# PolluxSensorTemp.net
KiCad netlist of a schematic drawn in EAGLE
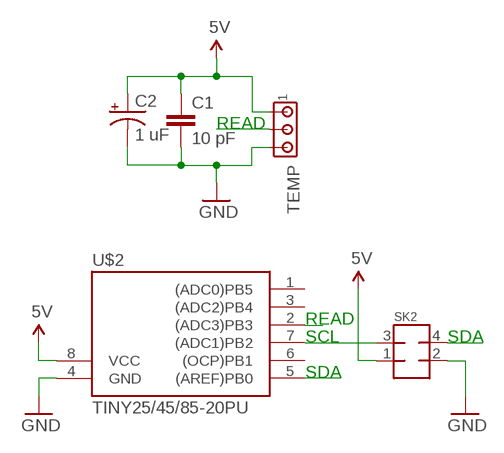
[diagram p0: schematic, sheet 1]

(export (version "E")
  (design (tool "Eeschema 10.0.6"))
  (components
    (comp (ref "C1")
      (value "10 pF")
      (footprint "eagle-import:CAP-PTH-5MM")
      (libsource (lib "eagle-import") (part "CAPPTH1"))
    )
    (comp (ref "C2")
      (value "1 uF")
      (footprint "eagle-import:CPOL-RADIAL-10UF-25V")
      (libsource (lib "eagle-import") (part "CAP_POLPTH2"))
    )
    (comp (ref "SK2")
      (value "MMATCH-8-PTH")
      (footprint "eagle-import:AMP-215079-8")
      (libsource (lib "eagle-import") (part "MMATCH-8-PTH"))
    )
    (comp (ref "TEMP")
      (value "MTA03-100")
      (footprint "eagle-import:10X03MTA")
      (libsource (lib "eagle-import") (part "MTA03-100"))
    )
    (comp (ref "U$2")
      (value "TINY25/45/85-20PU")
      (footprint "eagle-import:DIL08")
      (libsource (lib "eagle-import") (part "TINY25/45/85-20PU"))
    )
  )
  (nets
    (net (code "1") (name "/READ") (class "Default")
      (node (ref "TEMP") (pin "2") (pinfunction "2_2") (pintype "passive"))
      (node (ref "U$2") (pin "2") (pinfunction "(ADC3)PB3_2") (pintype "bidirectional"))
    )
    (net (code "2") (name "/SDA") (class "Default")
      (node (ref "SK2") (pin "4") (pinfunction "4_4") (pintype "bidirectional"))
      (node (ref "U$2") (pin "5") (pinfunction "(AREF)PB0_5") (pintype "bidirectional"))
    )
    (net (code "3") (name "5V") (class "Default")
      (node (ref "C1") (pin "1") (pinfunction "1_1") (pintype "passive"))
      (node (ref "C2") (pin "1") (pinfunction "+_1") (pintype "passive"))
      (node (ref "SK2") (pin "1") (pinfunction "1_1") (pintype "bidirectional"))
      (node (ref "TEMP") (pin "1") (pinfunction "1_1") (pintype "passive"))
      (node (ref "U$2") (pin "8") (pinfunction "VCC_8") (pintype "power_in"))
    )
    (net (code "4") (name "GND") (class "Default")
      (node (ref "C1") (pin "2") (pinfunction "2_2") (pintype "passive"))
      (node (ref "C2") (pin "2") (pinfunction "-_2") (pintype "passive"))
      (node (ref "SK2") (pin "2") (pinfunction "2_2") (pintype "bidirectional"))
      (node (ref "TEMP") (pin "3") (pinfunction "3_3") (pintype "passive"))
      (node (ref "U$2") (pin "4") (pinfunction "GND_4") (pintype "power_in"))
    )
    (net (code "5") (name "Net-(U$2-(ADC1)PB2)") (class "Default")
      (node (ref "SK2") (pin "3") (pinfunction "3_3") (pintype "bidirectional"))
      (node (ref "U$2") (pin "7") (pinfunction "(ADC1)PB2_7") (pintype "bidirectional"))
    )
    (net (code "6") (name "unconnected-(U$2-(ADC0)PB5-Pad1)") (class "Default")
      (node (ref "U$2") (pin "1") (pinfunction "(ADC0)PB5_1") (pintype "bidirectional"))
    )
    (net (code "7") (name "unconnected-(U$2-(ADC2)PB4-Pad3)") (class "Default")
      (node (ref "U$2") (pin "3") (pinfunction "(ADC2)PB4_3") (pintype "bidirectional"))
    )
    (net (code "8") (name "unconnected-(U$2-(OCP)PB1-Pad6)") (class "Default")
      (node (ref "U$2") (pin "6") (pinfunction "(OCP)PB1_6") (pintype "bidirectional"))
    )
  )
)
